# RFIDPswdAuth.net
KiCad netlist of a schematic drawn in EAGLE
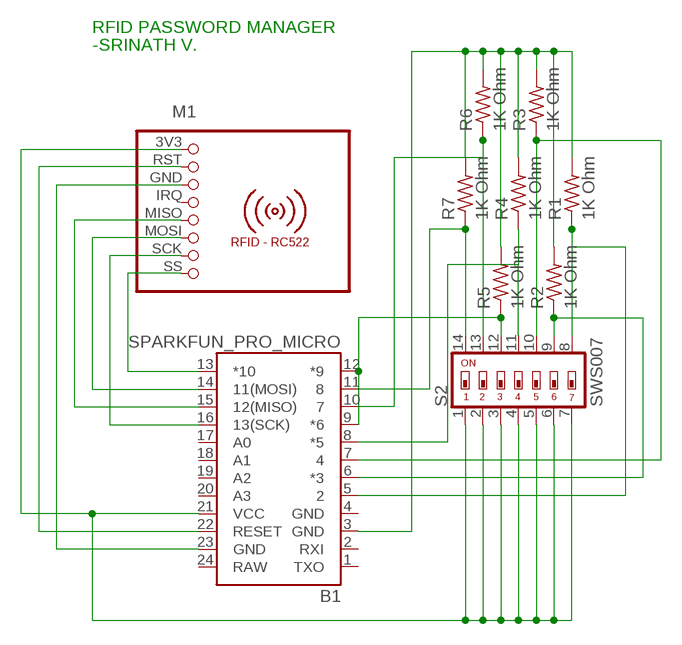
[diagram p0: schematic, sheet 1]

(export (version "E")
  (design (tool "Eeschema 10.0.6"))
  (components
    (comp (ref "B1")
      (value "SPARKFUN_PRO_MICRO")
      (footprint "eagle-import:SPARKFUN_PRO_MICRO")
      (libsource (lib "eagle-import") (part "SPARKFUN_PRO_MICRO"))
    )
    (comp (ref "M1")
      (value "RFID-RC522")
      (footprint "eagle-import:RFID-RC522")
      (libsource (lib "eagle-import") (part "RFID-RC522"))
    )
    (comp (ref "R1")
      (value "1K Ohm")
      (footprint "eagle-import:0204V")
      (libsource (lib "eagle-import") (part "R-US_0204/2V"))
    )
    (comp (ref "R2")
      (value "1K Ohm")
      (footprint "eagle-import:0204V")
      (libsource (lib "eagle-import") (part "R-US_0204/2V"))
    )
    (comp (ref "R3")
      (value "1K Ohm")
      (footprint "eagle-import:0204V")
      (libsource (lib "eagle-import") (part "R-US_0204/2V"))
    )
    (comp (ref "R4")
      (value "1K Ohm")
      (footprint "eagle-import:0204V")
      (libsource (lib "eagle-import") (part "R-US_0204/2V"))
    )
    (comp (ref "R5")
      (value "1K Ohm")
      (footprint "eagle-import:0204V")
      (libsource (lib "eagle-import") (part "R-US_0204/2V"))
    )
    (comp (ref "R6")
      (value "1K Ohm")
      (footprint "eagle-import:0204V")
      (libsource (lib "eagle-import") (part "R-US_0204/2V"))
    )
    (comp (ref "R7")
      (value "1K Ohm")
      (footprint "eagle-import:0204V")
      (libsource (lib "eagle-import") (part "R-US_0204/2V"))
    )
    (comp (ref "S2")
      (value "SWS007")
      (footprint "eagle-import:SMS-007")
      (libsource (lib "eagle-import") (part "SWS007"))
    )
  )
  (nets
    (net (code "1") (name "/GND") (class "Default")
      (node (ref "B1") (pin "4") (pinfunction "GND_4") (pintype "power_in"))
    )
    (net (code "2") (name "/RAW") (class "Default")
      (node (ref "B1") (pin "24") (pinfunction "RAW_24") (pintype "power_in"))
    )
    (net (code "3") (name "Net-(B1-*3)") (class "Default")
      (node (ref "B1") (pin "6") (pinfunction "*3_6") (pintype "bidirectional"))
      (node (ref "R2") (pin "1") (pinfunction "1_1") (pintype "passive"))
      (node (ref "S2") (pin "9") (pinfunction "9_9") (pintype "passive"))
    )
    (net (code "4") (name "Net-(B1-*5)") (class "Default")
      (node (ref "B1") (pin "8") (pinfunction "*5_8") (pintype "bidirectional"))
      (node (ref "R4") (pin "1") (pinfunction "1_1") (pintype "passive"))
      (node (ref "S2") (pin "11") (pinfunction "11_11") (pintype "passive"))
    )
    (net (code "5") (name "Net-(B1-*6)") (class "Default")
      (node (ref "B1") (pin "12") (pinfunction "*9_12") (pintype "bidirectional"))
      (node (ref "B1") (pin "9") (pinfunction "*6_9") (pintype "bidirectional"))
      (node (ref "R5") (pin "1") (pinfunction "1_1") (pintype "passive"))
      (node (ref "S2") (pin "12") (pinfunction "12_12") (pintype "passive"))
    )
    (net (code "6") (name "Net-(B1-*10)") (class "Default")
      (node (ref "B1") (pin "13") (pinfunction "*10_13") (pintype "bidirectional"))
      (node (ref "M1") (pin "SS") (pinfunction "8_SS") (pintype "passive"))
    )
    (net (code "7") (name "Net-(B1-2)") (class "Default")
      (node (ref "B1") (pin "5") (pinfunction "2_5") (pintype "bidirectional"))
      (node (ref "R1") (pin "1") (pinfunction "1_1") (pintype "passive"))
      (node (ref "S2") (pin "8") (pinfunction "8_8") (pintype "passive"))
    )
    (net (code "8") (name "Net-(B1-4)") (class "Default")
      (node (ref "B1") (pin "7") (pinfunction "4_7") (pintype "bidirectional"))
      (node (ref "R3") (pin "1") (pinfunction "1_1") (pintype "passive"))
      (node (ref "S2") (pin "10") (pinfunction "10_10") (pintype "passive"))
    )
    (net (code "9") (name "Net-(B1-7)") (class "Default")
      (node (ref "B1") (pin "10") (pinfunction "7_10") (pintype "bidirectional"))
      (node (ref "R6") (pin "1") (pinfunction "1_1") (pintype "passive"))
      (node (ref "S2") (pin "13") (pinfunction "13_13") (pintype "passive"))
    )
    (net (code "10") (name "Net-(B1-8)") (class "Default")
      (node (ref "B1") (pin "11") (pinfunction "8_11") (pintype "bidirectional"))
      (node (ref "R7") (pin "1") (pinfunction "1_1") (pintype "passive"))
      (node (ref "S2") (pin "14") (pinfunction "14_14") (pintype "passive"))
    )
    (net (code "11") (name "Net-(B1-11(MOSI))") (class "Default")
      (node (ref "B1") (pin "14") (pinfunction "11(MOSI)_14") (pintype "bidirectional"))
      (node (ref "M1") (pin "MOSI") (pinfunction "6_MOSI") (pintype "passive"))
    )
    (net (code "12") (name "Net-(B1-12(MISO))") (class "Default")
      (node (ref "B1") (pin "15") (pinfunction "12(MISO)_15") (pintype "bidirectional"))
      (node (ref "M1") (pin "MISO") (pinfunction "5_MISO") (pintype "passive"))
    )
    (net (code "13") (name "Net-(B1-13(SCK))") (class "Default")
      (node (ref "B1") (pin "16") (pinfunction "13(SCK)_16") (pintype "bidirectional"))
      (node (ref "M1") (pin "SCK") (pinfunction "7_SCK") (pintype "passive"))
    )
    (net (code "14") (name "Net-(B1-GND-Pad3)") (class "Default")
      (node (ref "B1") (pin "3") (pinfunction "GND_3") (pintype "power_in"))
      (node (ref "R1") (pin "2") (pinfunction "2_2") (pintype "passive"))
      (node (ref "R2") (pin "2") (pinfunction "2_2") (pintype "passive"))
      (node (ref "R3") (pin "2") (pinfunction "2_2") (pintype "passive"))
      (node (ref "R4") (pin "2") (pinfunction "2_2") (pintype "passive"))
      (node (ref "R5") (pin "2") (pinfunction "2_2") (pintype "passive"))
      (node (ref "R6") (pin "2") (pinfunction "2_2") (pintype "passive"))
      (node (ref "R7") (pin "2") (pinfunction "2_2") (pintype "passive"))
    )
    (net (code "15") (name "Net-(B1-RESET)") (class "Default")
      (node (ref "B1") (pin "22") (pinfunction "RESET_22") (pintype "bidirectional"))
      (node (ref "M1") (pin "RST") (pinfunction "2_RST") (pintype "passive"))
    )
    (net (code "16") (name "Net-(B1-VCC)") (class "Default")
      (node (ref "B1") (pin "21") (pinfunction "VCC_21") (pintype "power_in"))
      (node (ref "M1") (pin "3V3") (pinfunction "1_3V3") (pintype "passive"))
      (node (ref "S2") (pin "1") (pinfunction "1_1") (pintype "passive"))
      (node (ref "S2") (pin "2") (pinfunction "2_2") (pintype "passive"))
      (node (ref "S2") (pin "3") (pinfunction "3_3") (pintype "passive"))
      (node (ref "S2") (pin "4") (pinfunction "4_4") (pintype "passive"))
      (node (ref "S2") (pin "5") (pinfunction "5_5") (pintype "passive"))
      (node (ref "S2") (pin "6") (pinfunction "6_6") (pintype "passive"))
      (node (ref "S2") (pin "7") (pinfunction "7_7") (pintype "passive"))
    )
    (net (code "17") (name "Net-(M1-3)") (class "Default")
      (node (ref "B1") (pin "23") (pinfunction "GND_23") (pintype "power_in"))
      (node (ref "M1") (pin "GND") (pinfunction "3_GND") (pintype "passive"))
    )
    (net (code "18") (name "unconnected-(B1-A0-Pad17)") (class "Default")
      (node (ref "B1") (pin "17") (pinfunction "A0_17") (pintype "bidirectional"))
    )
    (net (code "19") (name "unconnected-(B1-A1-Pad18)") (class "Default")
      (node (ref "B1") (pin "18") (pinfunction "A1_18") (pintype "bidirectional"))
    )
    (net (code "20") (name "unconnected-(B1-A2-Pad19)") (class "Default")
      (node (ref "B1") (pin "19") (pinfunction "A2_19") (pintype "bidirectional"))
    )
    (net (code "21") (name "unconnected-(B1-A3-Pad20)") (class "Default")
      (node (ref "B1") (pin "20") (pinfunction "A3_20") (pintype "bidirectional"))
    )
    (net (code "22") (name "unconnected-(B1-RXI-Pad2)") (class "Default")
      (node (ref "B1") (pin "2") (pinfunction "RXI_2") (pintype "bidirectional"))
    )
    (net (code "23") (name "unconnected-(B1-TXO-Pad1)") (class "Default")
      (node (ref "B1") (pin "1") (pinfunction "TXO_1") (pintype "bidirectional"))
    )
    (net (code "24") (name "unconnected-(M1-4-PadIRQ)") (class "Default")
      (node (ref "M1") (pin "IRQ") (pinfunction "4_IRQ") (pintype "passive"))
    )
  )
)
